# m1_board.net
KiCad netlist of a schematic drawn in EAGLE
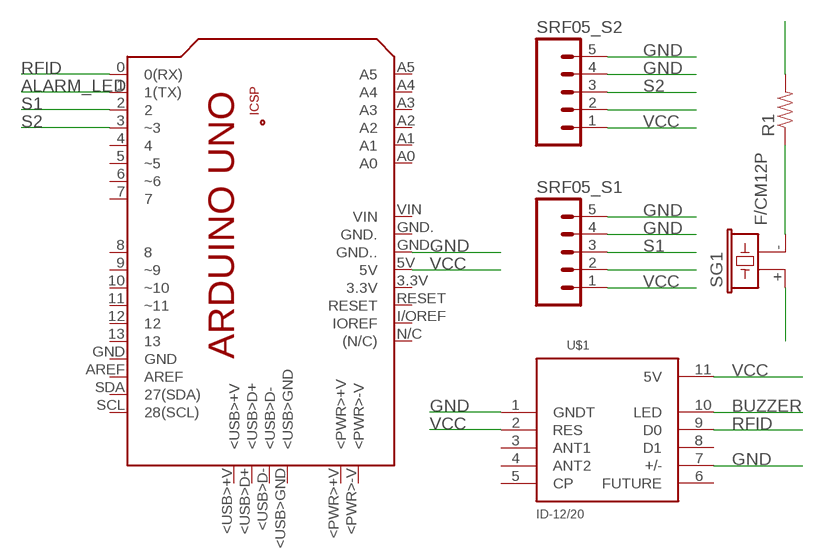
[diagram p0: schematic, sheet 1]

(export (version "E")
  (design (tool "Eeschema 10.0.6"))
  (components
    (comp (ref "PCB1")
      (value "ARDUINO_UNO")
      (footprint "eagle-import:ARDUINO_UNO")
      (libsource (lib "eagle-import") (part "ARDUINO_UNO"))
    )
    (comp (ref "R1")
      (value "RESISTORPTH-1/4W")
      (footprint "eagle-import:AXIAL-0.4")
      (libsource (lib "eagle-import") (part "RESISTORPTH-1/4W"))
    )
    (comp (ref "SG1")
      (value "F/CM12P")
      (footprint "eagle-import:F_CM12P")
      (libsource (lib "eagle-import") (part "F/CM12P"))
    )
    (comp (ref "SRF05_S1")
      (value "M05PTH")
      (footprint "eagle-import:1X05")
      (libsource (lib "eagle-import") (part "M05PTH"))
    )
    (comp (ref "SRF05_S2")
      (value "M05PTH")
      (footprint "eagle-import:1X05")
      (libsource (lib "eagle-import") (part "M05PTH"))
    )
    (comp (ref "U$1")
      (value "ID-12/20")
      (footprint "eagle-import:ID-12")
      (libsource (lib "eagle-import") (part "ID-12/20"))
    )
  )
  (nets
    (net (code "1") (name "/ALARM_LED") (class "Default")
      (node (ref "PCB1") (pin "1") (pinfunction "1(TX)_1") (pintype "bidirectional"))
    )
    (net (code "2") (name "/BUZZER") (class "Default")
      (node (ref "R1") (pin "P$2") (pinfunction "2_P$2") (pintype "passive"))
      (node (ref "U$1") (pin "10") (pinfunction "LED_10") (pintype "bidirectional"))
    )
    (net (code "3") (name "/GND") (class "Default")
      (node (ref "PCB1") (pin "GND..") (pinfunction "GND.._GND..") (pintype "bidirectional"))
      (node (ref "SRF05_S1") (pin "4") (pinfunction "4_4") (pintype "passive"))
      (node (ref "SRF05_S1") (pin "5") (pinfunction "5_5") (pintype "passive"))
      (node (ref "SRF05_S2") (pin "4") (pinfunction "4_4") (pintype "passive"))
      (node (ref "SRF05_S2") (pin "5") (pinfunction "5_5") (pintype "passive"))
      (node (ref "U$1") (pin "1") (pinfunction "GNDT_1") (pintype "bidirectional"))
      (node (ref "U$1") (pin "7") (pinfunction "+/-_7") (pintype "bidirectional"))
    )
    (net (code "4") (name "/RFID") (class "Default")
      (node (ref "PCB1") (pin "0") (pinfunction "0(RX)_0") (pintype "bidirectional"))
      (node (ref "U$1") (pin "9") (pinfunction "D0_9") (pintype "bidirectional"))
    )
    (net (code "5") (name "/S1") (class "Default")
      (node (ref "PCB1") (pin "2") (pinfunction "2_2") (pintype "bidirectional"))
      (node (ref "SRF05_S1") (pin "3") (pinfunction "3_3") (pintype "passive"))
    )
    (net (code "6") (name "/S2") (class "Default")
      (node (ref "PCB1") (pin "3") (pinfunction "~{3}_3") (pintype "bidirectional"))
      (node (ref "SRF05_S2") (pin "3") (pinfunction "3_3") (pintype "passive"))
    )
    (net (code "7") (name "/VCC") (class "Default")
      (node (ref "PCB1") (pin "5V") (pinfunction "5V_5V") (pintype "bidirectional"))
      (node (ref "SG1") (pin "+") (pinfunction "1_+") (pintype "passive"))
      (node (ref "SRF05_S1") (pin "1") (pinfunction "1_1") (pintype "passive"))
      (node (ref "SRF05_S2") (pin "1") (pinfunction "1_1") (pintype "passive"))
      (node (ref "U$1") (pin "11") (pinfunction "5V_11") (pintype "bidirectional"))
      (node (ref "U$1") (pin "2") (pinfunction "RES_2") (pintype "bidirectional"))
    )
    (net (code "8") (name "Net-(R1-1)") (class "Default")
      (node (ref "R1") (pin "P$1") (pinfunction "1_P$1") (pintype "passive"))
      (node (ref "SG1") (pin "-") (pinfunction "2_-") (pintype "passive"))
    )
    (net (code "9") (name "unconnected-(PCB1-(N{slash}C)-PadN{slash}C)") (class "Default")
      (node (ref "PCB1") (pin "N/C") (pinfunction "(N/C)_N/C") (pintype "bidirectional"))
    )
    (net (code "10") (name "unconnected-(PCB1-27(SDA)-PadSDA)") (class "Default")
      (node (ref "PCB1") (pin "SDA") (pinfunction "27(SDA)_SDA") (pintype "bidirectional"))
    )
    (net (code "11") (name "unconnected-(PCB1-28(SCL)-PadSCL)") (class "Default")
      (node (ref "PCB1") (pin "SCL") (pinfunction "28(SCL)_SCL") (pintype "bidirectional"))
    )
    (net (code "12") (name "unconnected-(PCB1-IOREF-PadI{slash}OREF)") (class "Default")
      (node (ref "PCB1") (pin "I/OREF") (pinfunction "IOREF_I/OREF") (pintype "bidirectional"))
    )
    (net (code "13") (name "unconnected-(PCB1-Pad+5V)") (class "Default")
      (node (ref "PCB1") (pin "+5V") (pinfunction "+5V_+5V") (pintype "bidirectional"))
    )
    (net (code "14") (name "unconnected-(PCB1-Pad3.3V)") (class "Default")
      (node (ref "PCB1") (pin "3.3V") (pinfunction "3.3V_3.3V") (pintype "bidirectional"))
    )
    (net (code "15") (name "unconnected-(PCB1-Pad4)") (class "Default")
      (node (ref "PCB1") (pin "4") (pinfunction "4_4") (pintype "bidirectional"))
    )
    (net (code "16") (name "unconnected-(PCB1-Pad7)") (class "Default")
      (node (ref "PCB1") (pin "7") (pinfunction "7_7") (pintype "bidirectional"))
    )
    (net (code "17") (name "unconnected-(PCB1-Pad8)") (class "Default")
      (node (ref "PCB1") (pin "8") (pinfunction "8_8") (pintype "bidirectional"))
    )
    (net (code "18") (name "unconnected-(PCB1-Pad12)") (class "Default")
      (node (ref "PCB1") (pin "12") (pinfunction "12_12") (pintype "bidirectional"))
    )
    (net (code "19") (name "unconnected-(PCB1-Pad13)") (class "Default")
      (node (ref "PCB1") (pin "13") (pinfunction "13_13") (pintype "bidirectional"))
    )
    (net (code "20") (name "unconnected-(PCB1-Pad<PWR>+V)") (class "Default")
      (node (ref "PCB1") (pin "<PWR>+V") (pinfunction "<PWR>+V_<PWR>+V") (pintype "bidirectional"))
    )
    (net (code "21") (name "unconnected-(PCB1-Pad<PWR>-V)") (class "Default")
      (node (ref "PCB1") (pin "<PWR>-V") (pinfunction "<PWR>-V_<PWR>-V") (pintype "bidirectional"))
    )
    (net (code "22") (name "unconnected-(PCB1-Pad<USB>+V)") (class "Default")
      (node (ref "PCB1") (pin "<USB>+V") (pinfunction "<USB>+V_<USB>+V") (pintype "bidirectional"))
    )
    (net (code "23") (name "unconnected-(PCB1-Pad<USB>D+)") (class "Default")
      (node (ref "PCB1") (pin "<USB>D+") (pinfunction "<USB>D+_<USB>D+") (pintype "bidirectional"))
    )
    (net (code "24") (name "unconnected-(PCB1-Pad<USB>D-)") (class "Default")
      (node (ref "PCB1") (pin "<USB>D-") (pinfunction "<USB>D-_<USB>D-") (pintype "bidirectional"))
    )
    (net (code "25") (name "unconnected-(PCB1-Pad<USB>GND)") (class "Default")
      (node (ref "PCB1") (pin "<USB>GND") (pinfunction "<USB>GND_<USB>GND") (pintype "bidirectional"))
    )
    (net (code "26") (name "unconnected-(PCB1-PadA0)") (class "Default")
      (node (ref "PCB1") (pin "A0") (pinfunction "A0_A0") (pintype "bidirectional"))
    )
    (net (code "27") (name "unconnected-(PCB1-PadA1)") (class "Default")
      (node (ref "PCB1") (pin "A1") (pinfunction "A1_A1") (pintype "bidirectional"))
    )
    (net (code "28") (name "unconnected-(PCB1-PadA2)") (class "Default")
      (node (ref "PCB1") (pin "A2") (pinfunction "A2_A2") (pintype "bidirectional"))
    )
    (net (code "29") (name "unconnected-(PCB1-PadA3)") (class "Default")
      (node (ref "PCB1") (pin "A3") (pinfunction "A3_A3") (pintype "bidirectional"))
    )
    (net (code "30") (name "unconnected-(PCB1-PadA4)") (class "Default")
      (node (ref "PCB1") (pin "A4") (pinfunction "A4_A4") (pintype "bidirectional"))
    )
    (net (code "31") (name "unconnected-(PCB1-PadA5)") (class "Default")
      (node (ref "PCB1") (pin "A5") (pinfunction "A5_A5") (pintype "bidirectional"))
    )
    (net (code "32") (name "unconnected-(PCB1-PadAREF)") (class "Default")
      (node (ref "PCB1") (pin "AREF") (pinfunction "AREF_AREF") (pintype "bidirectional"))
    )
    (net (code "33") (name "unconnected-(PCB1-PadGND)") (class "Default")
      (node (ref "PCB1") (pin "GND") (pinfunction "GND_GND") (pintype "bidirectional"))
    )
    (net (code "34") (name "unconnected-(PCB1-PadGND.)") (class "Default")
      (node (ref "PCB1") (pin "GND.") (pinfunction "GND._GND.") (pintype "bidirectional"))
    )
    (net (code "35") (name "unconnected-(PCB1-PadGND_)") (class "Default")
      (node (ref "PCB1") (pin "GND_") (pinfunction "GND__GND_") (pintype "bidirectional"))
    )
    (net (code "36") (name "unconnected-(PCB1-PadMISO)") (class "Default")
      (node (ref "PCB1") (pin "MISO") (pinfunction "MISO_MISO") (pintype "bidirectional"))
    )
    (net (code "37") (name "unconnected-(PCB1-PadMOSI)") (class "Default")
      (node (ref "PCB1") (pin "MOSI") (pinfunction "MOSI_MOSI") (pintype "bidirectional"))
    )
    (net (code "38") (name "unconnected-(PCB1-PadRESET)") (class "Default")
      (node (ref "PCB1") (pin "RESET") (pinfunction "RESET_RESET") (pintype "bidirectional"))
    )
    (net (code "39") (name "unconnected-(PCB1-PadRESET.)") (class "Default")
      (node (ref "PCB1") (pin "RESET.") (pinfunction "RESET._RESET.") (pintype "bidirectional"))
    )
    (net (code "40") (name "unconnected-(PCB1-PadSCK)") (class "Default")
      (node (ref "PCB1") (pin "SCK") (pinfunction "SCK_SCK") (pintype "bidirectional"))
    )
    (net (code "41") (name "unconnected-(PCB1-PadVIN)") (class "Default")
      (node (ref "PCB1") (pin "VIN") (pinfunction "VIN_VIN") (pintype "bidirectional"))
    )
    (net (code "42") (name "unconnected-(PCB1-~{5}-Pad5)") (class "Default")
      (node (ref "PCB1") (pin "5") (pinfunction "~{5}_5") (pintype "bidirectional"))
    )
    (net (code "43") (name "unconnected-(PCB1-~{6}-Pad6)") (class "Default")
      (node (ref "PCB1") (pin "6") (pinfunction "~{6}_6") (pintype "bidirectional"))
    )
    (net (code "44") (name "unconnected-(PCB1-~{9}-Pad9)") (class "Default")
      (node (ref "PCB1") (pin "9") (pinfunction "~{9}_9") (pintype "bidirectional"))
    )
    (net (code "45") (name "unconnected-(PCB1-~{10}-Pad10)") (class "Default")
      (node (ref "PCB1") (pin "10") (pinfunction "~{10}_10") (pintype "bidirectional"))
    )
    (net (code "46") (name "unconnected-(PCB1-~{11}-Pad11)") (class "Default")
      (node (ref "PCB1") (pin "11") (pinfunction "~{11}_11") (pintype "bidirectional"))
    )
    (net (code "47") (name "unconnected-(SRF05_S1-Pad2)") (class "Default")
      (node (ref "SRF05_S1") (pin "2") (pinfunction "2_2") (pintype "passive"))
    )
    (net (code "48") (name "unconnected-(SRF05_S2-Pad2)") (class "Default")
      (node (ref "SRF05_S2") (pin "2") (pinfunction "2_2") (pintype "passive"))
    )
    (net (code "49") (name "unconnected-(U$1-ANT1-Pad3)") (class "Default")
      (node (ref "U$1") (pin "3") (pinfunction "ANT1_3") (pintype "bidirectional"))
    )
    (net (code "50") (name "unconnected-(U$1-ANT2-Pad4)") (class "Default")
      (node (ref "U$1") (pin "4") (pinfunction "ANT2_4") (pintype "bidirectional"))
    )
    (net (code "51") (name "unconnected-(U$1-CP-Pad5)") (class "Default")
      (node (ref "U$1") (pin "5") (pinfunction "CP_5") (pintype "bidirectional"))
    )
    (net (code "52") (name "unconnected-(U$1-D1-Pad8)") (class "Default")
      (node (ref "U$1") (pin "8") (pinfunction "D1_8") (pintype "bidirectional"))
    )
    (net (code "53") (name "unconnected-(U$1-FUTURE-Pad6)") (class "Default")
      (node (ref "U$1") (pin "6") (pinfunction "FUTURE_6") (pintype "bidirectional"))
    )
  )
)
